# BTS_V2.net
KiCad netlist of a schematic drawn in EAGLE
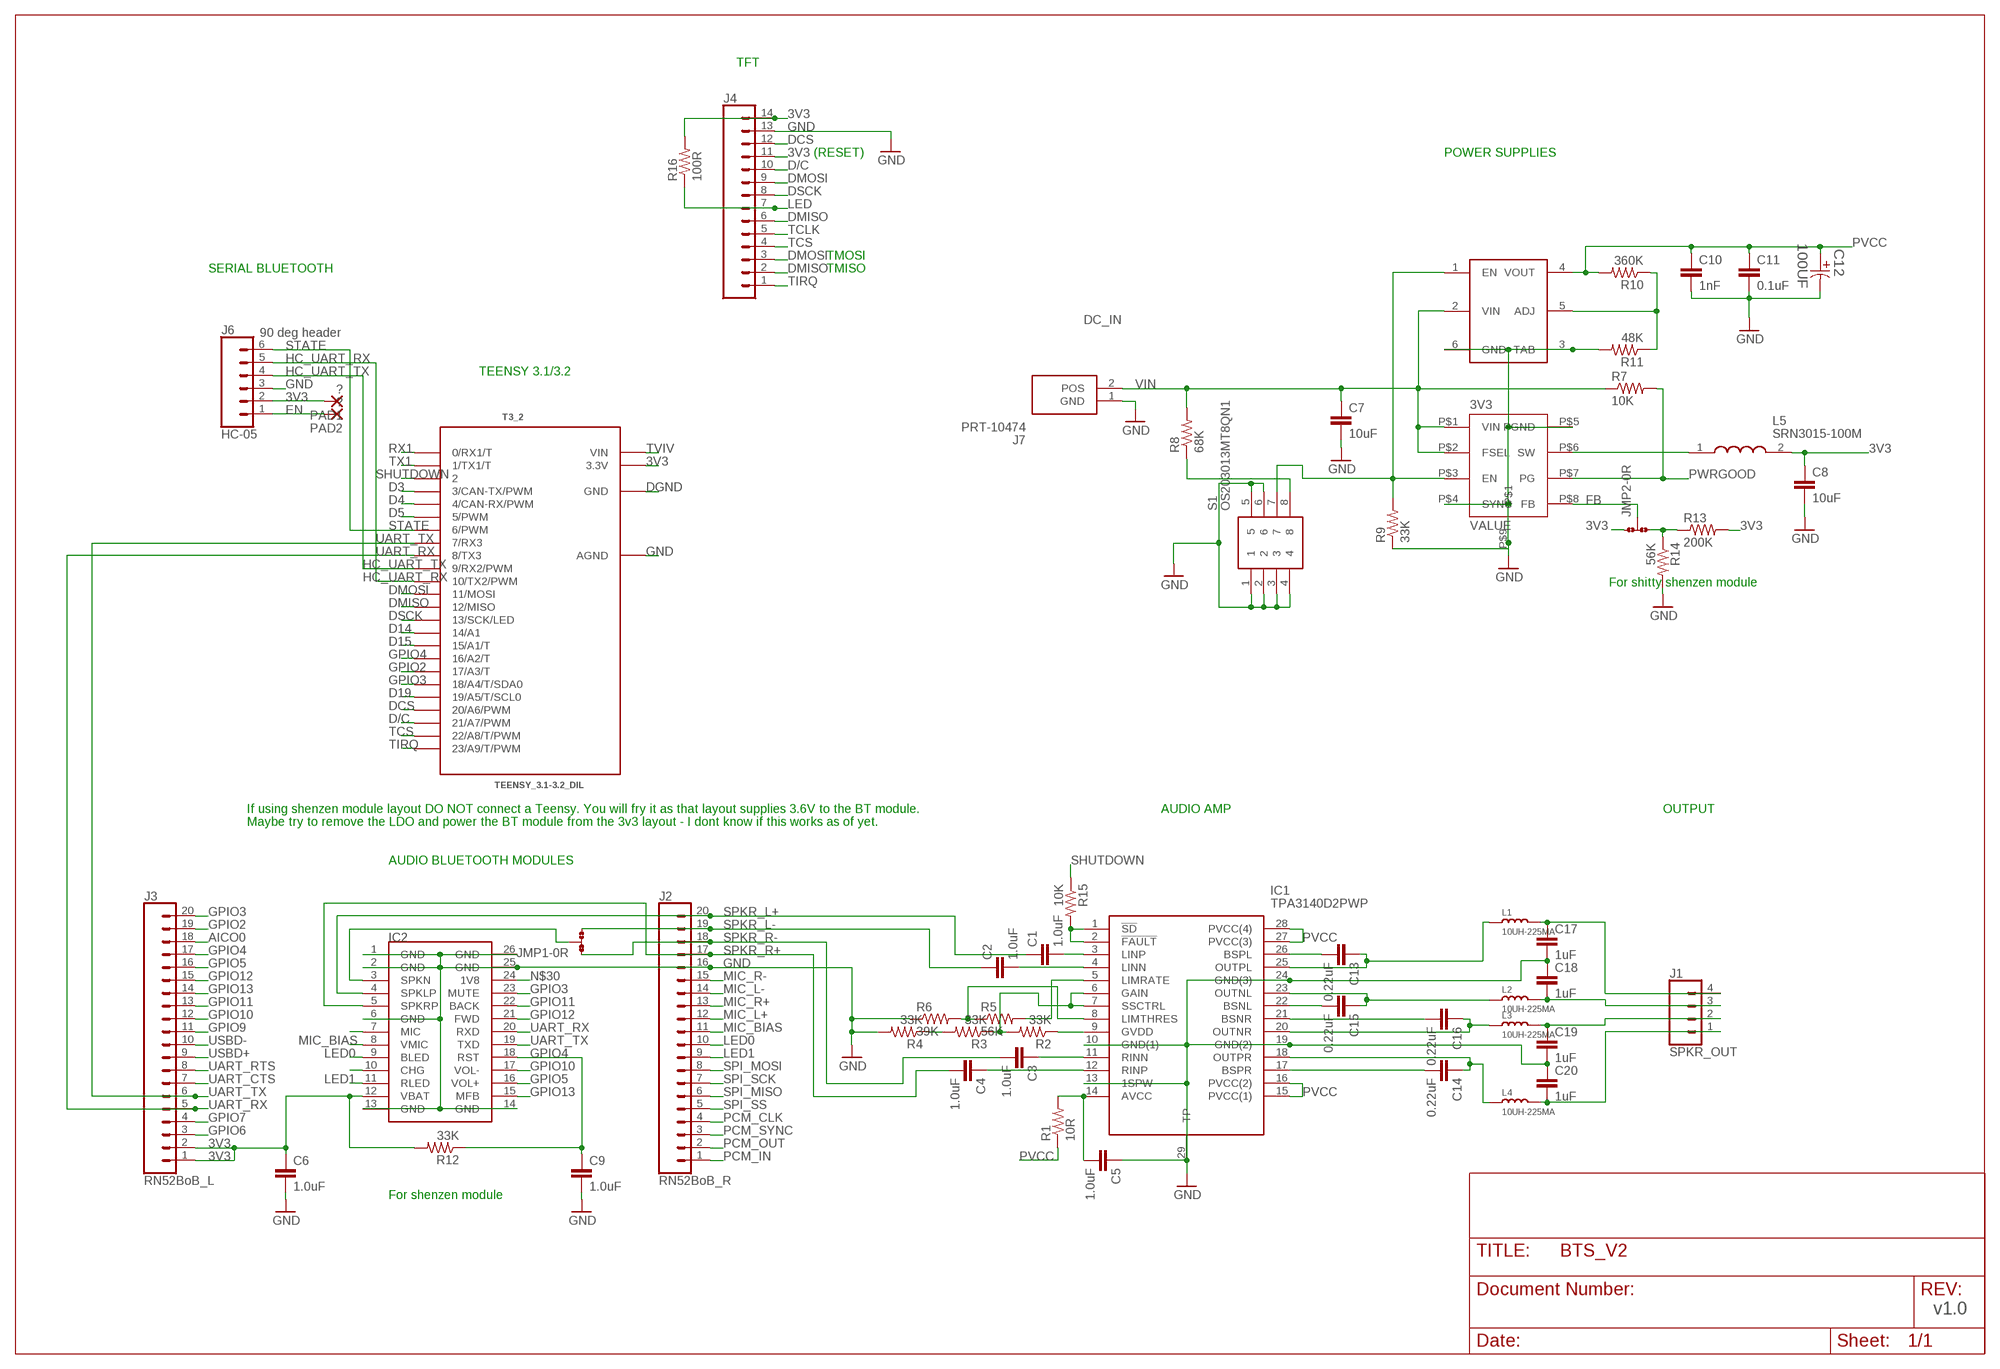
[diagram p0: schematic, sheet 1]

(export (version "E")
  (design (tool "Eeschema 10.0.6"))
  (components
    (comp (ref "3V3")
      (value "ADP2370")
      (footprint "eagle-import:3MM_LFCSP_QFN")
      (libsource (lib "eagle-import") (part "ADP2370"))
    )
    (comp (ref "C1")
      (value "1.0uF")
      (footprint "eagle-import:0603")
      (libsource (lib "eagle-import") (part "1.0UF-0603-16V-10%"))
    )
    (comp (ref "C2")
      (value "1.0uF")
      (footprint "eagle-import:0603")
      (libsource (lib "eagle-import") (part "1.0UF-0603-16V-10%"))
    )
    (comp (ref "C3")
      (value "1.0uF")
      (footprint "eagle-import:0603")
      (libsource (lib "eagle-import") (part "1.0UF-0603-16V-10%"))
    )
    (comp (ref "C4")
      (value "1.0uF")
      (footprint "eagle-import:0603")
      (libsource (lib "eagle-import") (part "1.0UF-0603-16V-10%"))
    )
    (comp (ref "C5")
      (value "1.0uF")
      (footprint "eagle-import:0603")
      (libsource (lib "eagle-import") (part "1.0UF-0603-16V-10%"))
    )
    (comp (ref "C6")
      (value "1.0uF")
      (footprint "eagle-import:0603")
      (libsource (lib "eagle-import") (part "1.0UF-0603-16V-10%"))
    )
    (comp (ref "C7")
      (value "10uF")
      (footprint "eagle-import:C3216")
      (fields (field (name "SPICEPREFIX") "10uF"))
      (libsource (lib "eagle-import") (part "C-EUC3216"))
    )
    (comp (ref "C8")
      (value "10uF")
      (footprint "eagle-import:C3216")
      (libsource (lib "eagle-import") (part "C-EUC3216"))
    )
    (comp (ref "C9")
      (value "1.0uF")
      (footprint "eagle-import:0603")
      (libsource (lib "eagle-import") (part "1.0UF-0603-16V-10%"))
    )
    (comp (ref "C10")
      (value "1nF")
      (footprint "eagle-import:0603")
      (libsource (lib "eagle-import") (part "1.0NF/1000PF-0603-50V-10%"))
    )
    (comp (ref "C11")
      (value "0.1uF")
      (footprint "eagle-import:0603")
      (libsource (lib "eagle-import") (part "0.1UF-0603-25V-(+80/-20%)"))
    )
    (comp (ref "C12")
      (value "100UF")
      (footprint "eagle-import:CAPAE660X610N")
      (fields (field (name "MPN") "EEE-FK1C101P") (field (name "TOLERANCE") "±20 %"))
      (libsource (lib "eagle-import") (part "EEE--CASE-DFK1C101P"))
    )
    (comp (ref "C13")
      (value "0.22uF")
      (footprint "eagle-import:0603")
      (libsource (lib "eagle-import") (part "0.22UF-0603-50V-(-20/+80%)"))
    )
    (comp (ref "C14")
      (value "0.22uF")
      (footprint "eagle-import:0603")
      (libsource (lib "eagle-import") (part "0.22UF-0603-50V-(-20/+80%)"))
    )
    (comp (ref "C15")
      (value "0.22uF")
      (footprint "eagle-import:0603")
      (libsource (lib "eagle-import") (part "0.22UF-0603-50V-(-20/+80%)"))
    )
    (comp (ref "C16")
      (value "0.22uF")
      (footprint "eagle-import:0603")
      (libsource (lib "eagle-import") (part "0.22UF-0603-50V-(-20/+80%)"))
    )
    (comp (ref "C17")
      (value "1uF")
      (footprint "eagle-import:0603")
      (libsource (lib "eagle-import") (part "1.0NF/1000PF-0603-50V-10%"))
    )
    (comp (ref "C18")
      (value "1uF")
      (footprint "eagle-import:0603")
      (libsource (lib "eagle-import") (part "1.0NF/1000PF-0603-50V-10%"))
    )
    (comp (ref "C19")
      (value "1uF")
      (footprint "eagle-import:0603")
      (libsource (lib "eagle-import") (part "1.0NF/1000PF-0603-50V-10%"))
    )
    (comp (ref "C20")
      (value "1uF")
      (footprint "eagle-import:0603")
      (libsource (lib "eagle-import") (part "1.0NF/1000PF-0603-50V-10%"))
    )
    (comp (ref "IC1")
      (value "TPA3140D2PWP")
      (footprint "eagle-import:SOP65P640X120-29N")
      (libsource (lib "eagle-import") (part "TPA3140D2PWP"))
    )
    (comp (ref "IC2")
      (value "BLK-MD-SPK-B")
      (footprint "eagle-import:BLK-MD-SPK-B")
      (libsource (lib "eagle-import") (part "BLK-MD-SPK-B"))
    )
    (comp (ref "J1")
      (value "SPKR_OUT")
      (footprint "eagle-import:SCREWTERMINAL-3.5MM-4")
      (libsource (lib "eagle-import") (part "CONN_04SCREW"))
    )
    (comp (ref "J2")
      (value "RN52BoB_R")
      (footprint "eagle-import:1X20")
      (libsource (lib "eagle-import") (part "CONN_20"))
    )
    (comp (ref "J3")
      (value "RN52BoB_L")
      (footprint "eagle-import:1X20")
      (libsource (lib "eagle-import") (part "CONN_20"))
    )
    (comp (ref "J4")
      (value "CONN_14")
      (footprint "eagle-import:1X14")
      (libsource (lib "eagle-import") (part "CONN_14"))
    )
    (comp (ref "J6")
      (value "HC-05")
      (footprint "eagle-import:1X06")
      (libsource (lib "eagle-import") (part "CONN_06SILK_FEMALE_PTH"))
    )
    (comp (ref "J7")
      (value "PRT-10474")
      (footprint "eagle-import:SHDR2W320P716_1X2_1574X813X158")
      (libsource (lib "eagle-import") (part "PRT-10474"))
    )
    (comp (ref "JMP1")
      (value "0R-JUMPA")
      (footprint "eagle-import:A0R-JMP")
      (libsource (lib "eagle-import") (part "0R-JUMPA"))
    )
    (comp (ref "JMP2")
      (value "0R-JUMPA")
      (footprint "eagle-import:A0R-JMP")
      (libsource (lib "eagle-import") (part "0R-JUMPA"))
    )
    (comp (ref "L1")
      (value "10UH-225MA")
      (footprint "eagle-import:L0806")
      (fields (field (name "MPN") "LQH2MCN100K02L"))
      (libsource (lib "eagle-import") (part "SMD-INDUCTOR-10UH-225MA-10%(0806)"))
    )
    (comp (ref "L2")
      (value "10UH-225MA")
      (footprint "eagle-import:L0806")
      (fields (field (name "MPN") "LQH2MCN100K02L"))
      (libsource (lib "eagle-import") (part "SMD-INDUCTOR-10UH-225MA-10%(0806)"))
    )
    (comp (ref "L3")
      (value "10UH-225MA")
      (footprint "eagle-import:L0806")
      (fields (field (name "MPN") "LQH2MCN100K02L"))
      (libsource (lib "eagle-import") (part "SMD-INDUCTOR-10UH-225MA-10%(0806)"))
    )
    (comp (ref "L4")
      (value "10UH-225MA")
      (footprint "eagle-import:L0806")
      (fields (field (name "MPN") "LQH2MCN100K02L"))
      (libsource (lib "eagle-import") (part "SMD-INDUCTOR-10UH-225MA-10%(0806)"))
    )
    (comp (ref "L5")
      (value "SRN3015-100M")
      (footprint "eagle-import:SRN3015")
      (fields (field (name "RS_PART_NUMBER") "7435071"))
      (libsource (lib "eagle-import") (part "SRN3015-100M"))
    )
    (comp (ref "PAD1")
      (value "?")
      (footprint "eagle-import:SMD1,27-2,54")
      (libsource (lib "eagle-import") (part "SMD2"))
    )
    (comp (ref "PAD2")
      (value "?")
      (footprint "eagle-import:SMD1,27-2,54")
      (libsource (lib "eagle-import") (part "SMD2"))
    )
    (comp (ref "R1")
      (value "10R")
      (footprint "eagle-import:R0603")
      (fields (field (name "RESISTANCE") "10R"))
      (libsource (lib "eagle-import") (part "R-US_R0603"))
    )
    (comp (ref "R2")
      (value "33K")
      (footprint "eagle-import:R0603")
      (fields (field (name "RESISTANCE") "33K"))
      (libsource (lib "eagle-import") (part "R-US_R0603"))
    )
    (comp (ref "R3")
      (value "33K")
      (footprint "eagle-import:R0603")
      (fields (field (name "RESISTANCE") "33K"))
      (libsource (lib "eagle-import") (part "R-US_R0603"))
    )
    (comp (ref "R4")
      (value "33K")
      (footprint "eagle-import:R0603")
      (fields (field (name "RESISTANCE") "33K"))
      (libsource (lib "eagle-import") (part "R-US_R0603"))
    )
    (comp (ref "R5")
      (value "56K")
      (footprint "eagle-import:R0603")
      (fields (field (name "RESISTANCE") "56K"))
      (libsource (lib "eagle-import") (part "R-US_R0603"))
    )
    (comp (ref "R6")
      (value "39K")
      (footprint "eagle-import:R0603")
      (fields (field (name "RESISTANCE") "39K"))
      (libsource (lib "eagle-import") (part "R-US_R0603"))
    )
    (comp (ref "R7")
      (value "10K")
      (footprint "eagle-import:R0603")
      (fields (field (name "RESISTANCE") "10K"))
      (libsource (lib "eagle-import") (part "R-US_R0603"))
    )
    (comp (ref "R8")
      (value "68K")
      (footprint "eagle-import:R0603")
      (fields (field (name "RESISTANCE") "68K"))
      (libsource (lib "eagle-import") (part "R-US_R0603"))
    )
    (comp (ref "R9")
      (value "33K")
      (footprint "eagle-import:R0603")
      (fields (field (name "RESISTANCE") "33K"))
      (libsource (lib "eagle-import") (part "R-US_R0603"))
    )
    (comp (ref "R10")
      (value "360K")
      (footprint "eagle-import:R0603")
      (fields (field (name "RESISTANCE") "10K"))
      (libsource (lib "eagle-import") (part "R-US_R0603"))
    )
    (comp (ref "R11")
      (value "48K")
      (footprint "eagle-import:R0603")
      (fields (field (name "RESISTANCE") "10K"))
      (libsource (lib "eagle-import") (part "R-US_R0603"))
    )
    (comp (ref "R12")
      (value "33K")
      (footprint "eagle-import:R0603")
      (fields (field (name "RESISTANCE") "33K"))
      (libsource (lib "eagle-import") (part "R-US_R0603"))
    )
    (comp (ref "R13")
      (value "200K")
      (footprint "eagle-import:R0603")
      (fields (field (name "RESISTANCE") "10K"))
      (libsource (lib "eagle-import") (part "R-US_R0603"))
    )
    (comp (ref "R14")
      (value "56K")
      (footprint "eagle-import:R0603")
      (fields (field (name "RESISTANCE") "10K"))
      (libsource (lib "eagle-import") (part "R-US_R0603"))
    )
    (comp (ref "R15")
      (value "10K")
      (footprint "eagle-import:R0603")
      (fields (field (name "RESISTANCE") "33K"))
      (libsource (lib "eagle-import") (part "R-US_R0603"))
    )
    (comp (ref "R16")
      (value "100R")
      (footprint "eagle-import:R0603")
      (libsource (lib "eagle-import") (part "R-US_R0603"))
    )
    (comp (ref "S1")
      (value "OS203013MT8QN1")
      (footprint "eagle-import:OS203013MT8QN1")
      (libsource (lib "eagle-import") (part "OS203013MT8QN1"))
    )
    (comp (ref "T3_2")
      (value "TEENSY_3.1-3.2_DIL")
      (footprint "eagle-import:TEENSY_3.0-3.2&LC_DIL")
      (libsource (lib "eagle-import") (part "TEENSY_3.1-3.2_DIL"))
    )
    (comp (ref "U$2")
      (value "NCP59302")
      (footprint "eagle-import:D2PAK-5")
      (libsource (lib "eagle-import") (part "NCP59302"))
    )
  )
  (nets
    (net (code "1") (name "/3V3") (class "Default")
      (node (ref "C6") (pin "1") (pinfunction "1_1") (pintype "passive"))
      (node (ref "C8") (pin "1") (pinfunction "1_1") (pintype "passive"))
      (node (ref "IC2") (pin "12") (pinfunction "VBAT_12") (pintype "bidirectional"))
      (node (ref "J3") (pin "1") (pinfunction "1_1") (pintype "passive"))
      (node (ref "J3") (pin "2") (pinfunction "2_2") (pintype "passive"))
      (node (ref "J4") (pin "11") (pinfunction "11_11") (pintype "passive"))
      (node (ref "J4") (pin "14") (pinfunction "14_14") (pintype "passive"))
      (node (ref "J6") (pin "2") (pinfunction "2_2") (pintype "passive"))
      (node (ref "JMP2") (pin "1") (pinfunction "1_1") (pintype "passive"))
      (node (ref "L5") (pin "2") (pinfunction "2_2") (pintype "input"))
      (node (ref "PAD1") (pin "1") (pinfunction "P_1") (pintype "passive"))
      (node (ref "R12") (pin "2") (pinfunction "2_2") (pintype "passive"))
      (node (ref "R13") (pin "2") (pinfunction "2_2") (pintype "passive"))
      (node (ref "R16") (pin "2") (pinfunction "2_2") (pintype "passive"))
      (node (ref "T3_2") (pin "3.3V") (pinfunction "3.3V_3.3V") (pintype "power_in"))
    )
    (net (code "2") (name "/AICO0") (class "Default")
      (node (ref "J3") (pin "18") (pinfunction "18_18") (pintype "passive"))
    )
    (net (code "3") (name "/D3") (class "Default")
      (node (ref "T3_2") (pin "3") (pinfunction "3/CAN-TX/PWM_3") (pintype "bidirectional"))
    )
    (net (code "4") (name "/D4") (class "Default")
      (node (ref "T3_2") (pin "4") (pinfunction "4/CAN-RX/PWM_4") (pintype "bidirectional"))
    )
    (net (code "5") (name "/D5") (class "Default")
      (node (ref "T3_2") (pin "5") (pinfunction "5/PWM_5") (pintype "bidirectional"))
    )
    (net (code "6") (name "/D14") (class "Default")
      (node (ref "T3_2") (pin "14/A0") (pinfunction "14/A1_14/A0") (pintype "bidirectional"))
    )
    (net (code "7") (name "/D15") (class "Default")
      (node (ref "T3_2") (pin "15/A1") (pinfunction "15/A1/T_15/A1") (pintype "bidirectional"))
    )
    (net (code "8") (name "/D19") (class "Default")
      (node (ref "T3_2") (pin "19/A5") (pinfunction "19/A5/T/SCL0_19/A5") (pintype "bidirectional"))
    )
    (net (code "9") (name "/DCS") (class "Default")
      (node (ref "J4") (pin "12") (pinfunction "12_12") (pintype "passive"))
      (node (ref "T3_2") (pin "20/A6") (pinfunction "20/A6/PWM_20/A6") (pintype "bidirectional"))
    )
    (net (code "10") (name "/DGND") (class "Default")
      (node (ref "T3_2") (pin "GND") (pinfunction "GND_GND") (pintype "power_in"))
    )
    (net (code "11") (name "/DMISO") (class "Default")
      (node (ref "J4") (pin "2") (pinfunction "2_2") (pintype "passive"))
      (node (ref "J4") (pin "6") (pinfunction "6_6") (pintype "passive"))
      (node (ref "T3_2") (pin "12") (pinfunction "12/MISO_12") (pintype "bidirectional"))
    )
    (net (code "12") (name "/DMOSI") (class "Default")
      (node (ref "J4") (pin "3") (pinfunction "3_3") (pintype "passive"))
      (node (ref "J4") (pin "9") (pinfunction "9_9") (pintype "passive"))
      (node (ref "T3_2") (pin "11") (pinfunction "11/MOSI_11") (pintype "bidirectional"))
    )
    (net (code "13") (name "/DSCK") (class "Default")
      (node (ref "J4") (pin "8") (pinfunction "8_8") (pintype "passive"))
      (node (ref "T3_2") (pin "13") (pinfunction "13/SCK/LED_13") (pintype "bidirectional"))
    )
    (net (code "14") (name "/D{slash}C") (class "Default")
      (node (ref "J4") (pin "10") (pinfunction "10_10") (pintype "passive"))
      (node (ref "T3_2") (pin "21/A7") (pinfunction "21/A7/PWM_21/A7") (pintype "bidirectional"))
    )
    (net (code "15") (name "/EN") (class "Default")
      (node (ref "J6") (pin "1") (pinfunction "1_1") (pintype "passive"))
      (node (ref "PAD2") (pin "1") (pinfunction "P_1") (pintype "passive"))
    )
    (net (code "16") (name "/FB") (class "Default")
      (node (ref "3V3") (pin "P$8") (pinfunction "FB_P$8") (pintype "bidirectional"))
      (node (ref "JMP2") (pin "2") (pinfunction "2_2") (pintype "passive"))
    )
    (net (code "17") (name "/GPIO2") (class "Default")
      (node (ref "J3") (pin "19") (pinfunction "19_19") (pintype "passive"))
      (node (ref "T3_2") (pin "17/A3") (pinfunction "17/A3/T_17/A3") (pintype "bidirectional"))
    )
    (net (code "18") (name "/GPIO3") (class "Default")
      (node (ref "IC2") (pin "23") (pinfunction "MUTE_23") (pintype "bidirectional"))
      (node (ref "J3") (pin "20") (pinfunction "20_20") (pintype "passive"))
      (node (ref "T3_2") (pin "18/A4") (pinfunction "18/A4/T/SDA0_18/A4") (pintype "bidirectional"))
    )
    (net (code "19") (name "/GPIO4") (class "Default")
      (node (ref "C9") (pin "1") (pinfunction "1_1") (pintype "passive"))
      (node (ref "IC2") (pin "18") (pinfunction "RST_18") (pintype "bidirectional"))
      (node (ref "J3") (pin "17") (pinfunction "17_17") (pintype "passive"))
      (node (ref "R12") (pin "1") (pinfunction "1_1") (pintype "passive"))
      (node (ref "T3_2") (pin "16/A2") (pinfunction "16/A2/T_16/A2") (pintype "bidirectional"))
    )
    (net (code "20") (name "/GPIO5") (class "Default")
      (node (ref "IC2") (pin "16") (pinfunction "VOL+_16") (pintype "bidirectional"))
      (node (ref "J3") (pin "16") (pinfunction "16_16") (pintype "passive"))
    )
    (net (code "21") (name "/GPIO6") (class "Default")
      (node (ref "J3") (pin "3") (pinfunction "3_3") (pintype "passive"))
    )
    (net (code "22") (name "/GPIO7") (class "Default")
      (node (ref "J3") (pin "4") (pinfunction "4_4") (pintype "passive"))
    )
    (net (code "23") (name "/GPIO9") (class "Default")
      (node (ref "J3") (pin "11") (pinfunction "11_11") (pintype "passive"))
    )
    (net (code "24") (name "/GPIO10") (class "Default")
      (node (ref "IC2") (pin "17") (pinfunction "VOL-_17") (pintype "bidirectional"))
      (node (ref "J3") (pin "12") (pinfunction "12_12") (pintype "passive"))
    )
    (net (code "25") (name "/GPIO11") (class "Default")
      (node (ref "IC2") (pin "22") (pinfunction "BACK_22") (pintype "bidirectional"))
      (node (ref "J3") (pin "13") (pinfunction "13_13") (pintype "passive"))
    )
    (net (code "26") (name "/GPIO12") (class "Default")
      (node (ref "IC2") (pin "21") (pinfunction "FWD_21") (pintype "bidirectional"))
      (node (ref "J3") (pin "15") (pinfunction "15_15") (pintype "passive"))
    )
    (net (code "27") (name "/GPIO13") (class "Default")
      (node (ref "IC2") (pin "15") (pinfunction "MFB_15") (pintype "bidirectional"))
      (node (ref "J3") (pin "14") (pinfunction "14_14") (pintype "passive"))
    )
    (net (code "28") (name "/HC_UART_RX") (class "Default")
      (node (ref "J6") (pin "5") (pinfunction "5_5") (pintype "passive"))
      (node (ref "T3_2") (pin "10") (pinfunction "10/TX2/PWM_10") (pintype "bidirectional"))
    )
    (net (code "29") (name "/HC_UART_TX") (class "Default")
      (node (ref "J6") (pin "4") (pinfunction "4_4") (pintype "passive"))
      (node (ref "T3_2") (pin "9") (pinfunction "9/RX2/PWM_9") (pintype "bidirectional"))
    )
    (net (code "30") (name "/LED") (class "Default")
      (node (ref "J4") (pin "7") (pinfunction "7_7") (pintype "passive"))
      (node (ref "R16") (pin "1") (pinfunction "1_1") (pintype "passive"))
    )
    (net (code "31") (name "/LED0") (class "Default")
      (node (ref "IC2") (pin "9") (pinfunction "BLED_9") (pintype "bidirectional"))
      (node (ref "J2") (pin "10") (pinfunction "10_10") (pintype "passive"))
    )
    (net (code "32") (name "/LED1") (class "Default")
      (node (ref "IC2") (pin "11") (pinfunction "RLED_11") (pintype "bidirectional"))
      (node (ref "J2") (pin "9") (pinfunction "9_9") (pintype "passive"))
    )
    (net (code "33") (name "/MIC_BIAS") (class "Default")
      (node (ref "IC2") (pin "8") (pinfunction "VMIC_8") (pintype "bidirectional"))
      (node (ref "J2") (pin "11") (pinfunction "11_11") (pintype "passive"))
    )
    (net (code "34") (name "/MIC_L+") (class "Default")
      (node (ref "J2") (pin "12") (pinfunction "12_12") (pintype "passive"))
    )
    (net (code "35") (name "/MIC_L-") (class "Default")
      (node (ref "J2") (pin "14") (pinfunction "14_14") (pintype "passive"))
    )
    (net (code "36") (name "/MIC_R+") (class "Default")
      (node (ref "J2") (pin "13") (pinfunction "13_13") (pintype "passive"))
    )
    (net (code "37") (name "/MIC_R-") (class "Default")
      (node (ref "J2") (pin "15") (pinfunction "15_15") (pintype "passive"))
    )
    (net (code "38") (name "/N$30") (class "Default")
      (node (ref "IC2") (pin "24") (pinfunction "1V8_24") (pintype "bidirectional"))
    )
    (net (code "39") (name "/PCM_CLK") (class "Default")
      (node (ref "J2") (pin "4") (pinfunction "4_4") (pintype "passive"))
    )
    (net (code "40") (name "/PCM_IN") (class "Default")
      (node (ref "J2") (pin "1") (pinfunction "1_1") (pintype "passive"))
    )
    (net (code "41") (name "/PCM_OUT") (class "Default")
      (node (ref "J2") (pin "2") (pinfunction "2_2") (pintype "passive"))
    )
    (net (code "42") (name "/PCM_SYNC") (class "Default")
      (node (ref "J2") (pin "3") (pinfunction "3_3") (pintype "passive"))
    )
    (net (code "43") (name "/PVCC") (class "Default")
      (node (ref "C10") (pin "1") (pinfunction "1_1") (pintype "passive"))
      (node (ref "C11") (pin "1") (pinfunction "1_1") (pintype "passive"))
      (node (ref "C12") (pin "1") (pinfunction "1_1") (pintype "passive"))
      (node (ref "IC1") (pin "15") (pinfunction "PVCC(1)_15") (pintype "input"))
      (node (ref "IC1") (pin "16") (pinfunction "PVCC(2)_16") (pintype "input"))
      (node (ref "IC1") (pin "27") (pinfunction "PVCC(3)_27") (pintype "input"))
      (node (ref "IC1") (pin "28") (pinfunction "PVCC(4)_28") (pintype "input"))
      (node (ref "R1") (pin "1") (pinfunction "1_1") (pintype "passive"))
      (node (ref "R10") (pin "2") (pinfunction "2_2") (pintype "passive"))
      (node (ref "U$2") (pin "4") (pinfunction "VOUT_4") (pintype "bidirectional"))
    )
    (net (code "44") (name "/PWRGOOD") (class "Default")
      (node (ref "3V3") (pin "P$7") (pinfunction "PG_P$7") (pintype "bidirectional"))
      (node (ref "R7") (pin "2") (pinfunction "2_2") (pintype "passive"))
    )
    (net (code "45") (name "/RX1") (class "Default")
      (node (ref "T3_2") (pin "0") (pinfunction "0/RX1/T_0") (pintype "bidirectional"))
    )
    (net (code "46") (name "/SHUTDOWN") (class "Default")
      (node (ref "R15") (pin "1") (pinfunction "1_1") (pintype "passive"))
      (node (ref "T3_2") (pin "2") (pinfunction "2_2") (pintype "bidirectional"))
    )
    (net (code "47") (name "/SPI_MISO") (class "Default")
      (node (ref "J2") (pin "6") (pinfunction "6_6") (pintype "passive"))
    )
    (net (code "48") (name "/SPI_MOSI") (class "Default")
      (node (ref "J2") (pin "8") (pinfunction "8_8") (pintype "passive"))
    )
    (net (code "49") (name "/SPI_SCK") (class "Default")
      (node (ref "J2") (pin "7") (pinfunction "7_7") (pintype "passive"))
    )
    (net (code "50") (name "/SPI_SS") (class "Default")
      (node (ref "J2") (pin "5") (pinfunction "5_5") (pintype "passive"))
    )
    (net (code "51") (name "/SPKR_L+") (class "Default")
      (node (ref "C1") (pin "1") (pinfunction "1_1") (pintype "passive"))
      (node (ref "IC2") (pin "4") (pinfunction "SPKLP_4") (pintype "bidirectional"))
      (node (ref "J2") (pin "20") (pinfunction "20_20") (pintype "passive"))
    )
    (net (code "52") (name "/SPKR_L-") (class "Default")
      (node (ref "C2") (pin "1") (pinfunction "1_1") (pintype "passive"))
      (node (ref "J2") (pin "19") (pinfunction "19_19") (pintype "passive"))
      (node (ref "JMP1") (pin "3") (pinfunction "3_3") (pintype "passive"))
    )
    (net (code "53") (name "/SPKR_R+") (class "Default")
      (node (ref "C4") (pin "2") (pinfunction "2_2") (pintype "passive"))
      (node (ref "IC2") (pin "5") (pinfunction "SPKRP_5") (pintype "bidirectional"))
      (node (ref "J2") (pin "17") (pinfunction "17_17") (pintype "passive"))
    )
    (net (code "54") (name "/SPKR_R-") (class "Default")
      (node (ref "C3") (pin "2") (pinfunction "2_2") (pintype "passive"))
      (node (ref "J2") (pin "18") (pinfunction "18_18") (pintype "passive"))
      (node (ref "JMP1") (pin "1") (pinfunction "1_1") (pintype "passive"))
    )
    (net (code "55") (name "/STATE") (class "Default")
      (node (ref "J6") (pin "6") (pinfunction "6_6") (pintype "passive"))
      (node (ref "T3_2") (pin "6") (pinfunction "6/PWM_6") (pintype "bidirectional"))
    )
    (net (code "56") (name "/TCLK") (class "Default")
      (node (ref "J4") (pin "5") (pinfunction "5_5") (pintype "passive"))
    )
    (net (code "57") (name "/TCS") (class "Default")
      (node (ref "J4") (pin "4") (pinfunction "4_4") (pintype "passive"))
      (node (ref "T3_2") (pin "22/A8") (pinfunction "22/A8/T/PWM_22/A8") (pintype "bidirectional"))
    )
    (net (code "58") (name "/TIRQ") (class "Default")
      (node (ref "J4") (pin "1") (pinfunction "1_1") (pintype "passive"))
      (node (ref "T3_2") (pin "23/A9") (pinfunction "23/A9/T/PWM_23/A9") (pintype "bidirectional"))
    )
    (net (code "59") (name "/TVIV") (class "Default")
      (node (ref "T3_2") (pin "VIN") (pinfunction "VIN_VIN") (pintype "power_in"))
    )
    (net (code "60") (name "/TX1") (class "Default")
      (node (ref "T3_2") (pin "1") (pinfunction "1/TX1/T_1") (pintype "bidirectional"))
    )
    (net (code "61") (name "/UART_CTS") (class "Default")
      (node (ref "J3") (pin "7") (pinfunction "7_7") (pintype "passive"))
    )
    (net (code "62") (name "/UART_RTS") (class "Default")
      (node (ref "J3") (pin "8") (pinfunction "8_8") (pintype "passive"))
    )
    (net (code "63") (name "/UART_RX") (class "Default")
      (node (ref "IC2") (pin "20") (pinfunction "RXD_20") (pintype "bidirectional"))
      (node (ref "J3") (pin "5") (pinfunction "5_5") (pintype "passive"))
      (node (ref "T3_2") (pin "8") (pinfunction "8/TX3_8") (pintype "bidirectional"))
    )
    (net (code "64") (name "/UART_TX") (class "Default")
      (node (ref "IC2") (pin "19") (pinfunction "TXD_19") (pintype "bidirectional"))
      (node (ref "J3") (pin "6") (pinfunction "6_6") (pintype "passive"))
      (node (ref "T3_2") (pin "7") (pinfunction "7/RX3_7") (pintype "bidirectional"))
    )
    (net (code "65") (name "/USBD+") (class "Default")
      (node (ref "J3") (pin "9") (pinfunction "9_9") (pintype "passive"))
    )
    (net (code "66") (name "/USBD-") (class "Default")
      (node (ref "J3") (pin "10") (pinfunction "10_10") (pintype "passive"))
    )
    (net (code "67") (name "/VIN") (class "Default")
      (node (ref "3V3") (pin "P$1") (pinfunction "VIN_P$1") (pintype "bidirectional"))
      (node (ref "3V3") (pin "P$2") (pinfunction "FSEL_P$2") (pintype "bidirectional"))
      (node (ref "C7") (pin "1") (pinfunction "1_1") (pintype "passive"))
      (node (ref "J7") (pin "2") (pinfunction "POS_2") (pintype "input"))
      (node (ref "R7") (pin "1") (pinfunction "1_1") (pintype "passive"))
      (node (ref "R8") (pin "2") (pinfunction "2_2") (pintype "passive"))
      (node (ref "U$2") (pin "2") (pinfunction "VIN_2") (pintype "bidirectional"))
    )
    (net (code "68") (name "GND") (class "Default")
      (node (ref "3V3") (pin "P$4") (pinfunction "SYNC_P$4") (pintype "bidirectional"))
      (node (ref "3V3") (pin "P$5") (pinfunction "PGND_P$5") (pintype "bidirectional"))
      (node (ref "3V3") (pin "P$9") (pinfunction "P$1_P$9") (pintype "bidirectional"))
      (node (ref "C10") (pin "2") (pinfunction "2_2") (pintype "passive"))
      (node (ref "C11") (pin "2") (pinfunction "2_2") (pintype "passive"))
      (node (ref "C12") (pin "2") (pinfunction "2_2") (pintype "passive"))
      (node (ref "C17") (pin "2") (pinfunction "2_2") (pintype "passive"))
      (node (ref "C18") (pin "1") (pinfunction "1_1") (pintype "passive"))
      (node (ref "C19") (pin "2") (pinfunction "2_2") (pintype "passive"))
      (node (ref "C20") (pin "1") (pinfunction "1_1") (pintype "passive"))
      (node (ref "C5") (pin "1") (pinfunction "1_1") (pintype "passive"))
      (node (ref "C6") (pin "2") (pinfunction "2_2") (pintype "passive"))
      (node (ref "C7") (pin "2") (pinfunction "2_2") (pintype "passive"))
      (node (ref "C8") (pin "2") (pinfunction "2_2") (pintype "passive"))
      (node (ref "C9") (pin "2") (pinfunction "2_2") (pintype "passive"))
      (node (ref "IC1") (pin "10") (pinfunction "GND(1)_10") (pintype "input"))
      (node (ref "IC1") (pin "13") (pinfunction "1SPW_13") (pintype "input"))
      (node (ref "IC1") (pin "19") (pinfunction "GND(2)_19") (pintype "input"))
      (node (ref "IC1") (pin "24") (pinfunction "GND(3)_24") (pintype "input"))
      (node (ref "IC1") (pin "29") (pinfunction "TP_29") (pintype "input"))
      (node (ref "IC2") (pin "1") (pinfunction "GND_1") (pintype "bidirectional"))
      (node (ref "IC2") (pin "13") (pinfunction "GND_13") (pintype "bidirectional"))
      (node (ref "IC2") (pin "14") (pinfunction "GND_14") (pintype "bidirectional"))
      (node (ref "IC2") (pin "2") (pinfunction "GND_2") (pintype "bidirectional"))
      (node (ref "IC2") (pin "25") (pinfunction "GND_25") (pintype "bidirectional"))
      (node (ref "IC2") (pin "26") (pinfunction "GND_26") (pintype "bidirectional"))
      (node (ref "IC2") (pin "6") (pinfunction "GND_6") (pintype "bidirectional"))
      (node (ref "J2") (pin "16") (pinfunction "16_16") (pintype "passive"))
      (node (ref "J4") (pin "13") (pinfunction "13_13") (pintype "passive"))
      (node (ref "J6") (pin "3") (pinfunction "3_3") (pintype "passive"))
      (node (ref "J7") (pin "1") (pinfunction "GND_1") (pintype "input"))
      (node (ref "R11") (pin "2") (pinfunction "2_2") (pintype "passive"))
      (node (ref "R14") (pin "2") (pinfunction "2_2") (pintype "passive"))
      (node (ref "R4") (pin "2") (pinfunction "2_2") (pintype "passive"))
      (node (ref "R6") (pin "1") (pinfunction "1_1") (pintype "passive"))
      (node (ref "R9") (pin "1") (pinfunction "1_1") (pintype "passive"))
      (node (ref "S1") (pin "1") (pinfunction "1_1") (pintype "input"))
      (node (ref "S1") (pin "2") (pinfunction "2_2") (pintype "input"))
      (node (ref "S1") (pin "3") (pinfunction "3_3") (pintype "input"))
      (node (ref "S1") (pin "4") (pinfunction "4_4") (pintype "input"))
      (node (ref "S1") (pin "5") (pinfunction "5_5") (pintype "input"))
      (node (ref "S1") (pin "6") (pinfunction "6_6") (pintype "input"))
      (node (ref "T3_2") (pin "AGND") (pinfunction "AGND_AGND") (pintype "power_in"))
      (node (ref "U$2") (pin "3") (pinfunction "TAB_3") (pintype "bidirectional"))
      (node (ref "U$2") (pin "6") (pinfunction "GND_6") (pintype "bidirectional"))
    )
    (net (code "69") (name "Net-(3V3-EN)") (class "Default")
      (node (ref "3V3") (pin "P$3") (pinfunction "EN_P$3") (pintype "bidirectional"))
      (node (ref "R9") (pin "2") (pinfunction "2_2") (pintype "passive"))
      (node (ref "S1") (pin "7") (pinfunction "7_7") (pintype "input"))
      (node (ref "U$2") (pin "1") (pinfunction "EN_1") (pintype "bidirectional"))
    )
    (net (code "70") (name "Net-(3V3-SW)") (class "Default")
      (node (ref "3V3") (pin "P$6") (pinfunction "SW_P$6") (pintype "bidirectional"))
      (node (ref "L5") (pin "1") (pinfunction "1_1") (pintype "input"))
    )
    (net (code "71") (name "Net-(C17-Pad1)") (class "Default")
      (node (ref "C17") (pin "1") (pinfunction "1_1") (pintype "passive"))
      (node (ref "J1") (pin "4") (pinfunction "4_4") (pintype "passive"))
      (node (ref "L1") (pin "2") (pinfunction "2_2") (pintype "passive"))
    )
    (net (code "72") (name "Net-(C18-Pad2)") (class "Default")
      (node (ref "C18") (pin "2") (pinfunction "2_2") (pintype "passive"))
      (node (ref "J1") (pin "3") (pinfunction "3_3") (pintype "passive"))
      (node (ref "L2") (pin "2") (pinfunction "2_2") (pintype "passive"))
    )
    (net (code "73") (name "Net-(C19-Pad1)") (class "Default")
      (node (ref "C19") (pin "1") (pinfunction "1_1") (pintype "passive"))
      (node (ref "J1") (pin "2") (pinfunction "2_2") (pintype "passive"))
      (node (ref "L3") (pin "2") (pinfunction "2_2") (pintype "passive"))
    )
    (net (code "74") (name "Net-(C20-Pad2)") (class "Default")
      (node (ref "C20") (pin "2") (pinfunction "2_2") (pintype "passive"))
      (node (ref "J1") (pin "1") (pinfunction "1_1") (pintype "passive"))
      (node (ref "L4") (pin "2") (pinfunction "2_2") (pintype "passive"))
    )
    (net (code "75") (name "Net-(IC1-AVCC)") (class "Default")
      (node (ref "C5") (pin "2") (pinfunction "2_2") (pintype "passive"))
      (node (ref "IC1") (pin "14") (pinfunction "AVCC_14") (pintype "input"))
      (node (ref "R1") (pin "2") (pinfunction "2_2") (pintype "passive"))
    )
    (net (code "76") (name "Net-(IC1-BSNL)") (class "Default")
      (node (ref "C15") (pin "2") (pinfunction "2_2") (pintype "passive"))
      (node (ref "IC1") (pin "22") (pinfunction "BSNL_22") (pintype "input"))
    )
    (net (code "77") (name "Net-(IC1-BSNR)") (class "Default")
      (node (ref "C16") (pin "2") (pinfunction "2_2") (pintype "passive"))
      (node (ref "IC1") (pin "21") (pinfunction "BSNR_21") (pintype "input"))
    )
    (net (code "78") (name "Net-(IC1-BSPL)") (class "Default")
      (node (ref "C13") (pin "2") (pinfunction "2_2") (pintype "passive"))
      (node (ref "IC1") (pin "26") (pinfunction "BSPL_26") (pintype "input"))
    )
    (net (code "79") (name "Net-(IC1-BSPR)") (class "Default")
      (node (ref "C14") (pin "2") (pinfunction "2_2") (pintype "passive"))
      (node (ref "IC1") (pin "17") (pinfunction "BSPR_17") (pintype "input"))
    )
    (net (code "80") (name "Net-(IC1-GAIN)") (class "Default")
      (node (ref "IC1") (pin "6") (pinfunction "GAIN_6") (pintype "input"))
      (node (ref "IC1") (pin "7") (pinfunction "SSCTRL_7") (pintype "input"))
      (node (ref "R2") (pin "2") (pinfunction "2_2") (pintype "passive"))
      (node (ref "R3") (pin "1") (pinfunction "1_1") (pintype "passive"))
    )
    (net (code "81") (name "Net-(IC1-GVDD)") (class "Default")
      (node (ref "IC1") (pin "9") (pinfunction "GVDD_9") (pintype "input"))
      (node (ref "R2") (pin "1") (pinfunction "1_1") (pintype "passive"))
    )
    (net (code "82") (name "Net-(IC1-LIMRATE)") (class "Default")
      (node (ref "IC1") (pin "5") (pinfunction "LIMRATE_5") (pintype "input"))
      (node (ref "R5") (pin "2") (pinfunction "2_2") (pintype "passive"))
    )
    (net (code "83") (name "Net-(IC1-LIMTHRES)") (class "Default")
      (node (ref "IC1") (pin "8") (pinfunction "LIMTHRES_8") (pintype "input"))
      (node (ref "R5") (pin "1") (pinfunction "1_1") (pintype "passive"))
      (node (ref "R6") (pin "2") (pinfunction "2_2") (pintype "passive"))
    )
    (net (code "84") (name "Net-(IC1-LINN)") (class "Default")
      (node (ref "C2") (pin "2") (pinfunction "2_2") (pintype "passive"))
      (node (ref "IC1") (pin "4") (pinfunction "LINN_4") (pintype "input"))
    )
    (net (code "85") (name "Net-(IC1-LINP)") (class "Default")
      (node (ref "C1") (pin "2") (pinfunction "2_2") (pintype "passive"))
      (node (ref "IC1") (pin "3") (pinfunction "LINP_3") (pintype "input"))
    )
    (net (code "86") (name "Net-(IC1-OUTNL)") (class "Default")
      (node (ref "C15") (pin "1") (pinfunction "1_1") (pintype "passive"))
      (node (ref "IC1") (pin "23") (pinfunction "OUTNL_23") (pintype "input"))
      (node (ref "L2") (pin "1") (pinfunction "1_1") (pintype "passive"))
    )
    (net (code "87") (name "Net-(IC1-OUTNR)") (class "Default")
      (node (ref "C16") (pin "1") (pinfunction "1_1") (pintype "passive"))
      (node (ref "IC1") (pin "20") (pinfunction "OUTNR_20") (pintype "input"))
      (node (ref "L3") (pin "1") (pinfunction "1_1") (pintype "passive"))
    )
    (net (code "88") (name "Net-(IC1-OUTPL)") (class "Default")
      (node (ref "C13") (pin "1") (pinfunction "1_1") (pintype "passive"))
      (node (ref "IC1") (pin "25") (pinfunction "OUTPL_25") (pintype "input"))
      (node (ref "L1") (pin "1") (pinfunction "1_1") (pintype "passive"))
    )
    (net (code "89") (name "Net-(IC1-OUTPR)") (class "Default")
      (node (ref "C14") (pin "1") (pinfunction "1_1") (pintype "passive"))
      (node (ref "IC1") (pin "18") (pinfunction "OUTPR_18") (pintype "input"))
      (node (ref "L4") (pin "1") (pinfunction "1_1") (pintype "passive"))
    )
    (net (code "90") (name "Net-(IC1-RINN)") (class "Default")
      (node (ref "C3") (pin "1") (pinfunction "1_1") (pintype "passive"))
      (node (ref "IC1") (pin "11") (pinfunction "RINN_11") (pintype "input"))
    )
    (net (code "91") (name "Net-(IC1-RINP)") (class "Default")
      (node (ref "C4") (pin "1") (pinfunction "1_1") (pintype "passive"))
      (node (ref "IC1") (pin "12") (pinfunction "RINP_12") (pintype "input"))
    )
    (net (code "92") (name "Net-(IC1-~{FAULT})") (class "Default")
      (node (ref "IC1") (pin "1") (pinfunction "~{SD}_1") (pintype "input"))
      (node (ref "IC1") (pin "2") (pinfunction "~{FAULT}_2") (pintype "input"))
      (node (ref "R15") (pin "2") (pinfunction "2_2") (pintype "passive"))
    )
    (net (code "93") (name "Net-(IC2-SPKN)") (class "Default")
      (node (ref "IC2") (pin "3") (pinfunction "SPKN_3") (pintype "bidirectional"))
      (node (ref "JMP1") (pin "2") (pinfunction "2_2") (pintype "passive"))
    )
    (net (code "94") (name "Net-(JMP2-Pad3)") (class "Default")
      (node (ref "JMP2") (pin "3") (pinfunction "3_3") (pintype "passive"))
      (node (ref "R13") (pin "1") (pinfunction "1_1") (pintype "passive"))
      (node (ref "R14") (pin "1") (pinfunction "1_1") (pintype "passive"))
    )
    (net (code "95") (name "Net-(R3-Pad2)") (class "Default")
      (node (ref "R3") (pin "2") (pinfunction "2_2") (pintype "passive"))
      (node (ref "R4") (pin "1") (pinfunction "1_1") (pintype "passive"))
    )
    (net (code "96") (name "Net-(R8-Pad1)") (class "Default")
      (node (ref "R8") (pin "1") (pinfunction "1_1") (pintype "passive"))
      (node (ref "S1") (pin "8") (pinfunction "8_8") (pintype "input"))
    )
    (net (code "97") (name "Net-(U$2-ADJ)") (class "Default")
      (node (ref "R10") (pin "1") (pinfunction "1_1") (pintype "passive"))
      (node (ref "R11") (pin "1") (pinfunction "1_1") (pintype "passive"))
      (node (ref "U$2") (pin "5") (pinfunction "ADJ_5") (pintype "bidirectional"))
    )
    (net (code "98") (name "unconnected-(IC2-CHG-Pad10)") (class "Default")
      (node (ref "IC2") (pin "10") (pinfunction "CHG_10") (pintype "bidirectional"))
    )
    (net (code "99") (name "unconnected-(IC2-MIC-Pad7)") (class "Default")
      (node (ref "IC2") (pin "7") (pinfunction "MIC_7") (pintype "bidirectional"))
    )
  )
)
